# Sheet3.net
KiCad netlist of a schematic drawn in Altium Designer
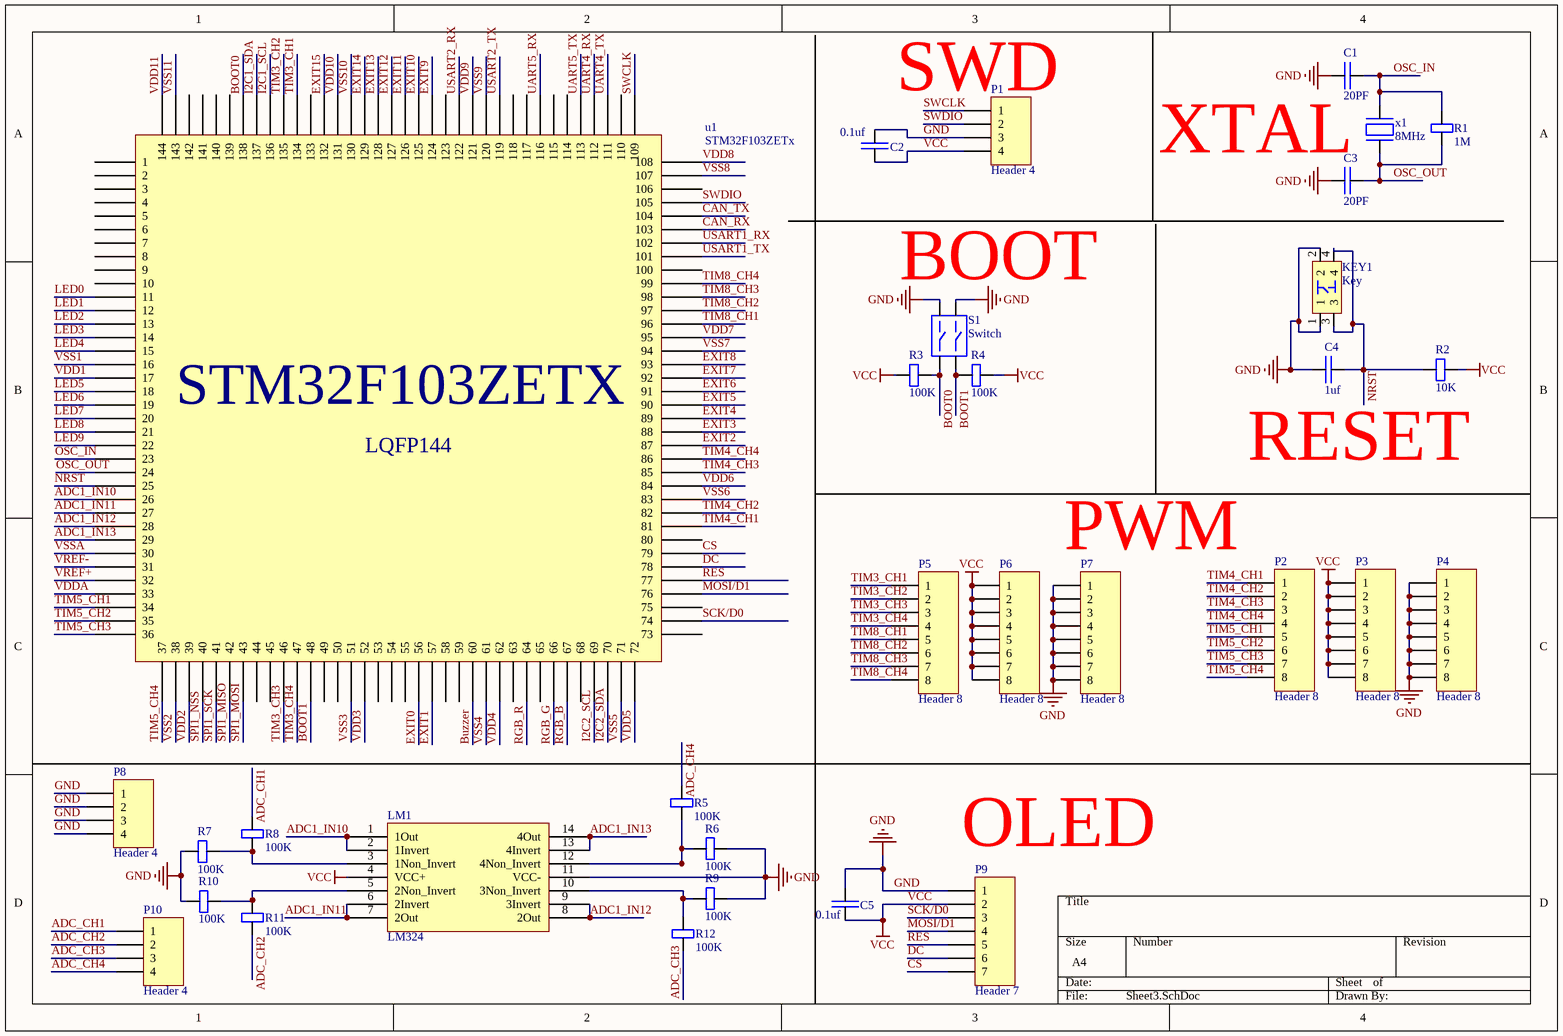
[diagram p0: Sheet3.SchDoc]

(export (version "E")
  (design (tool "Eeschema 10.0.6"))
  (components
    (comp (ref "C1") (value "20PF") (footprint "0402") (libsource (lib "Schlib1") (part "C")))
    (comp (ref "C2") (value "0.1uf") (footprint "0402") (libsource (lib "Schlib1") (part "C")))
    (comp (ref "C3") (value "20PF") (footprint "0402") (libsource (lib "Schlib1") (part "C")))
    (comp (ref "C4") (value "1uf") (footprint "0402") (libsource (lib "Schlib1") (part "C")))
    (comp (ref "C5") (value "0.1uf") (footprint "0402") (libsource (lib "Schlib1") (part "C")))
    (comp (ref "KEY1") (value "Key") (footprint "6*6*5轻触开关") (libsource (lib "Schlib1") (part "Key")))
    (comp (ref "LM1") (value "LM324") (footprint "LM324") (libsource (lib "Schlib1") (part "LM324")))
    (comp (ref "P1")
      (value "Header 4")
      (footprint "HDR1X4")
      (description "Header, 4-Pin")
      (fields (field (name "PUBLISHER") "Altium Limited"))
      (libsource (lib "Miscellaneous Connectors") (part "Header 4"))
    )
    (comp (ref "P2")
      (value "Header 8")
      (footprint "HDR1X8")
      (description "Header, 8-Pin")
      (fields (field (name "PUBLISHER") "Altium Limited"))
      (libsource (lib "Miscellaneous Connectors") (part "Header 8"))
    )
    (comp (ref "P3")
      (value "Header 8")
      (footprint "HDR1X8")
      (description "Header, 8-Pin")
      (fields (field (name "PUBLISHER") "Altium Limited"))
      (libsource (lib "Miscellaneous Connectors") (part "Header 8"))
    )
    (comp (ref "P4")
      (value "Header 8")
      (footprint "HDR1X8")
      (description "Header, 8-Pin")
      (fields (field (name "PUBLISHER") "Altium Limited"))
      (libsource (lib "Miscellaneous Connectors") (part "Header 8"))
    )
    (comp (ref "P5")
      (value "Header 8")
      (footprint "HDR1X8")
      (description "Header, 8-Pin")
      (fields (field (name "PUBLISHER") "Altium Limited"))
      (libsource (lib "Miscellaneous Connectors") (part "Header 8"))
    )
    (comp (ref "P6")
      (value "Header 8")
      (footprint "HDR1X8")
      (description "Header, 8-Pin")
      (fields (field (name "PUBLISHER") "Altium Limited"))
      (libsource (lib "Miscellaneous Connectors") (part "Header 8"))
    )
    (comp (ref "P7")
      (value "Header 8")
      (footprint "HDR1X8")
      (description "Header, 8-Pin")
      (fields (field (name "PUBLISHER") "Altium Limited"))
      (libsource (lib "Miscellaneous Connectors") (part "Header 8"))
    )
    (comp (ref "P8")
      (value "Header 4")
      (footprint "HDR1X4")
      (description "Header, 4-Pin")
      (fields (field (name "PUBLISHER") "Altium Limited"))
      (libsource (lib "Miscellaneous Connectors") (part "Header 4"))
    )
    (comp (ref "P9")
      (value "Header 7")
      (footprint "HDR1X7")
      (description "Header, 7-Pin")
      (fields (field (name "PUBLISHER") "Altium Limited"))
      (libsource (lib "Miscellaneous Connectors") (part "Header 7"))
    )
    (comp (ref "P10")
      (value "Header 4")
      (footprint "HDR1X4")
      (description "Header, 4-Pin")
      (fields (field (name "PUBLISHER") "Altium Limited"))
      (libsource (lib "Miscellaneous Connectors") (part "Header 4"))
    )
    (comp (ref "R1") (value "1M") (footprint "0402") (libsource (lib "Schlib1") (part "R")))
    (comp (ref "R2") (value "10K") (footprint "0402") (libsource (lib "Schlib1") (part "R")))
    (comp (ref "R3") (value "100K") (footprint "0402") (libsource (lib "Schlib1") (part "R")))
    (comp (ref "R4") (value "100K") (footprint "0402") (libsource (lib "Schlib1") (part "R")))
    (comp (ref "R5") (value "100K") (footprint "0402") (libsource (lib "Schlib1") (part "R")))
    (comp (ref "R6") (value "100K") (footprint "0402") (libsource (lib "Schlib1") (part "R")))
    (comp (ref "R7") (value "100K") (footprint "0402") (libsource (lib "Schlib1") (part "R")))
    (comp (ref "R8") (value "100K") (footprint "0402") (libsource (lib "Schlib1") (part "R")))
    (comp (ref "R9") (value "100K") (footprint "0402") (libsource (lib "Schlib1") (part "R")))
    (comp (ref "R10") (value "100K") (footprint "0402") (libsource (lib "Schlib1") (part "R")))
    (comp (ref "R11") (value "100K") (footprint "0402") (libsource (lib "Schlib1") (part "R")))
    (comp (ref "R12") (value "100K") (footprint "0402") (libsource (lib "Schlib1") (part "R")))
    (comp (ref "S1") (value "Switch") (footprint "SWITCH_2P") (libsource (lib "Schlib1") (part "Switch")))
    (comp (ref "u1")
      (value "STM32F103ZETx")
      (footprint "STM32F103ZETx")
      (libsource (lib "Schlib1") (part "STM32F103ZETx"))
    )
    (comp (ref "x1") (value "8MHz") (footprint "8M晶振") (libsource (lib "Schlib1") (part "XTAL_8MHz")))
  )
  (nets
    (net (code "1") (name "/ADC1_IN10") (class "Default")
      (node (ref "LM1") (pin "1") (pinfunction "1Out_1") (pintype "passive"))
      (node (ref "LM1") (pin "2") (pinfunction "1Invert_2") (pintype "passive"))
      (node (ref "u1") (pin "26") (pinfunction "26_26") (pintype "passive"))
    )
    (net (code "2") (name "/ADC1_IN11") (class "Default")
      (node (ref "LM1") (pin "6") (pinfunction "2Invert_6") (pintype "passive"))
      (node (ref "LM1") (pin "7") (pinfunction "2Out_7") (pintype "passive"))
      (node (ref "u1") (pin "27") (pinfunction "27_27") (pintype "passive"))
    )
    (net (code "3") (name "/ADC1_IN12") (class "Default")
      (node (ref "LM1") (pin "8") (pinfunction "2Out_8") (pintype "passive"))
      (node (ref "LM1") (pin "9") (pinfunction "3Invert_9") (pintype "passive"))
      (node (ref "u1") (pin "28") (pinfunction "28_28") (pintype "passive"))
    )
    (net (code "4") (name "/ADC1_IN13") (class "Default")
      (node (ref "LM1") (pin "13") (pinfunction "4Invert_13") (pintype "passive"))
      (node (ref "LM1") (pin "14") (pinfunction "4Out_14") (pintype "passive"))
      (node (ref "u1") (pin "29") (pinfunction "29_29") (pintype "passive"))
    )
    (net (code "5") (name "/ADC_CH1") (class "Default")
      (node (ref "P10") (pin "1") (pinfunction "1_1") (pintype "passive"))
      (node (ref "R8") (pin "2") (pinfunction "2_2") (pintype "passive"))
    )
    (net (code "6") (name "/ADC_CH2") (class "Default")
      (node (ref "P10") (pin "2") (pinfunction "2_2") (pintype "passive"))
      (node (ref "R11") (pin "2") (pinfunction "2_2") (pintype "passive"))
    )
    (net (code "7") (name "/ADC_CH3") (class "Default")
      (node (ref "P10") (pin "3") (pinfunction "3_3") (pintype "passive"))
      (node (ref "R12") (pin "2") (pinfunction "2_2") (pintype "passive"))
    )
    (net (code "8") (name "/ADC_CH4") (class "Default")
      (node (ref "P10") (pin "4") (pinfunction "4_4") (pintype "passive"))
      (node (ref "R5") (pin "1") (pinfunction "1_1") (pintype "passive"))
    )
    (net (code "9") (name "/BOOT0") (class "Default")
      (node (ref "R3") (pin "1") (pinfunction "1_1") (pintype "passive"))
      (node (ref "S1") (pin "2") (pinfunction "156_2") (pintype "passive"))
      (node (ref "u1") (pin "138") (pinfunction "138_138") (pintype "passive"))
    )
    (net (code "10") (name "/BOOT1") (class "Default")
      (node (ref "R4") (pin "2") (pinfunction "2_2") (pintype "passive"))
      (node (ref "S1") (pin "4") (pinfunction "157_4") (pintype "passive"))
      (node (ref "u1") (pin "48") (pinfunction "48_48") (pintype "passive"))
    )
    (net (code "11") (name "/Buzzer") (class "Default")
      (node (ref "u1") (pin "60") (pinfunction "60_60") (pintype "passive"))
    )
    (net (code "12") (name "/CAN_RX") (class "Default")
      (node (ref "u1") (pin "103") (pinfunction "103_103") (pintype "passive"))
    )
    (net (code "13") (name "/CAN_TX") (class "Default")
      (node (ref "u1") (pin "104") (pinfunction "104_104") (pintype "passive"))
    )
    (net (code "14") (name "/CS") (class "Default")
      (node (ref "P9") (pin "7") (pinfunction "7_7") (pintype "passive"))
      (node (ref "u1") (pin "79") (pinfunction "79_79") (pintype "passive"))
    )
    (net (code "15") (name "/DC") (class "Default")
      (node (ref "P9") (pin "6") (pinfunction "6_6") (pintype "passive"))
      (node (ref "u1") (pin "78") (pinfunction "78_78") (pintype "passive"))
    )
    (net (code "16") (name "/EXIT0") (class "Default")
      (node (ref "u1") (pin "56") (pinfunction "56_56") (pintype "passive"))
    )
    (net (code "17") (name "/EXIT1") (class "Default")
      (node (ref "u1") (pin "57") (pinfunction "57_57") (pintype "passive"))
    )
    (net (code "18") (name "/EXIT2") (class "Default")
      (node (ref "u1") (pin "87") (pinfunction "87_87") (pintype "passive"))
    )
    (net (code "19") (name "/EXIT3") (class "Default")
      (node (ref "u1") (pin "88") (pinfunction "88_88") (pintype "passive"))
    )
    (net (code "20") (name "/EXIT4") (class "Default")
      (node (ref "u1") (pin "89") (pinfunction "89_89") (pintype "passive"))
    )
    (net (code "21") (name "/EXIT5") (class "Default")
      (node (ref "u1") (pin "90") (pinfunction "90_90") (pintype "passive"))
    )
    (net (code "22") (name "/EXIT6") (class "Default")
      (node (ref "u1") (pin "91") (pinfunction "91_91") (pintype "passive"))
    )
    (net (code "23") (name "/EXIT7") (class "Default")
      (node (ref "u1") (pin "92") (pinfunction "92_92") (pintype "passive"))
    )
    (net (code "24") (name "/EXIT8") (class "Default")
      (node (ref "u1") (pin "93") (pinfunction "93_93") (pintype "passive"))
    )
    (net (code "25") (name "/EXIT9") (class "Default")
      (node (ref "u1") (pin "124") (pinfunction "124_124") (pintype "passive"))
    )
    (net (code "26") (name "/EXIT10") (class "Default")
      (node (ref "u1") (pin "125") (pinfunction "125_125") (pintype "passive"))
    )
    (net (code "27") (name "/EXIT11") (class "Default")
      (node (ref "u1") (pin "126") (pinfunction "126_126") (pintype "passive"))
    )
    (net (code "28") (name "/EXIT12") (class "Default")
      (node (ref "u1") (pin "127") (pinfunction "127_127") (pintype "passive"))
    )
    (net (code "29") (name "/EXIT13") (class "Default")
      (node (ref "u1") (pin "128") (pinfunction "128_128") (pintype "passive"))
    )
    (net (code "30") (name "/EXIT14") (class "Default")
      (node (ref "u1") (pin "129") (pinfunction "129_129") (pintype "passive"))
    )
    (net (code "31") (name "/EXIT15") (class "Default")
      (node (ref "u1") (pin "132") (pinfunction "132_132") (pintype "passive"))
    )
    (net (code "32") (name "/I2C1_SCL") (class "Default")
      (node (ref "u1") (pin "136") (pinfunction "136_136") (pintype "passive"))
    )
    (net (code "33") (name "/I2C1_SDA") (class "Default")
      (node (ref "u1") (pin "137") (pinfunction "137_137") (pintype "passive"))
    )
    (net (code "34") (name "/I2C2_SCL") (class "Default")
      (node (ref "u1") (pin "69") (pinfunction "69_69") (pintype "passive"))
    )
    (net (code "35") (name "/I2C2_SDA") (class "Default")
      (node (ref "u1") (pin "70") (pinfunction "70_70") (pintype "passive"))
    )
    (net (code "36") (name "/LED0") (class "Default")
      (node (ref "u1") (pin "11") (pinfunction "11_11") (pintype "passive"))
    )
    (net (code "37") (name "/LED1") (class "Default")
      (node (ref "u1") (pin "12") (pinfunction "12_12") (pintype "passive"))
    )
    (net (code "38") (name "/LED2") (class "Default")
      (node (ref "u1") (pin "13") (pinfunction "13_13") (pintype "passive"))
    )
    (net (code "39") (name "/LED3") (class "Default")
      (node (ref "u1") (pin "14") (pinfunction "14_14") (pintype "passive"))
    )
    (net (code "40") (name "/LED4") (class "Default")
      (node (ref "u1") (pin "15") (pinfunction "15_15") (pintype "passive"))
    )
    (net (code "41") (name "/LED5") (class "Default")
      (node (ref "u1") (pin "18") (pinfunction "18_18") (pintype "passive"))
    )
    (net (code "42") (name "/LED6") (class "Default")
      (node (ref "u1") (pin "19") (pinfunction "19_19") (pintype "passive"))
    )
    (net (code "43") (name "/LED7") (class "Default")
      (node (ref "u1") (pin "20") (pinfunction "20_20") (pintype "passive"))
    )
    (net (code "44") (name "/LED8") (class "Default")
      (node (ref "u1") (pin "21") (pinfunction "21_21") (pintype "passive"))
    )
    (net (code "45") (name "/LED9") (class "Default")
      (node (ref "u1") (pin "22") (pinfunction "22_22") (pintype "passive"))
    )
    (net (code "46") (name "/MOSI{slash}D1") (class "Default")
      (node (ref "P9") (pin "4") (pinfunction "4_4") (pintype "passive"))
      (node (ref "u1") (pin "76") (pinfunction "76_76") (pintype "passive"))
    )
    (net (code "47") (name "/NRST") (class "Default")
      (node (ref "C4") (pin "1") (pinfunction "1_1") (pintype "passive"))
      (node (ref "KEY1") (pin "3") (pinfunction "3_3") (pintype "passive"))
      (node (ref "KEY1") (pin "4") (pinfunction "4_4") (pintype "passive"))
      (node (ref "R2") (pin "1") (pinfunction "1_1") (pintype "passive"))
      (node (ref "u1") (pin "25") (pinfunction "25_25") (pintype "passive"))
    )
    (net (code "48") (name "/OSC_IN") (class "Default")
      (node (ref "C1") (pin "1") (pinfunction "1_1") (pintype "passive"))
      (node (ref "R1") (pin "2") (pinfunction "2_2") (pintype "passive"))
      (node (ref "u1") (pin "23") (pinfunction "23_23") (pintype "passive"))
      (node (ref "x1") (pin "1") (pinfunction "1_1") (pintype "passive"))
    )
    (net (code "49") (name "/OSC_OUT") (class "Default")
      (node (ref "C3") (pin "1") (pinfunction "1_1") (pintype "passive"))
      (node (ref "R1") (pin "1") (pinfunction "1_1") (pintype "passive"))
      (node (ref "u1") (pin "24") (pinfunction "24_24") (pintype "passive"))
      (node (ref "x1") (pin "2") (pinfunction "2_2") (pintype "passive"))
    )
    (net (code "50") (name "/RES") (class "Default")
      (node (ref "P9") (pin "5") (pinfunction "5_5") (pintype "passive"))
      (node (ref "u1") (pin "77") (pinfunction "77_77") (pintype "passive"))
    )
    (net (code "51") (name "/RGB_B") (class "Default")
      (node (ref "u1") (pin "67") (pinfunction "67_67") (pintype "passive"))
    )
    (net (code "52") (name "/RGB_G") (class "Default")
      (node (ref "u1") (pin "66") (pinfunction "66_66") (pintype "passive"))
    )
    (net (code "53") (name "/RGB_R") (class "Default")
      (node (ref "u1") (pin "64") (pinfunction "64_64") (pintype "passive"))
    )
    (net (code "54") (name "/SCK{slash}D0") (class "Default")
      (node (ref "P9") (pin "3") (pinfunction "3_3") (pintype "passive"))
      (node (ref "u1") (pin "74") (pinfunction "74_74") (pintype "passive"))
    )
    (net (code "55") (name "/SPI1_MISO") (class "Default")
      (node (ref "u1") (pin "42") (pinfunction "42_42") (pintype "passive"))
    )
    (net (code "56") (name "/SPI1_MOSI") (class "Default")
      (node (ref "u1") (pin "43") (pinfunction "43_43") (pintype "passive"))
    )
    (net (code "57") (name "/SPI1_NSS") (class "Default")
      (node (ref "u1") (pin "40") (pinfunction "40_40") (pintype "passive"))
    )
    (net (code "58") (name "/SPI1_SCK") (class "Default")
      (node (ref "u1") (pin "41") (pinfunction "41_41") (pintype "passive"))
    )
    (net (code "59") (name "/SWCLK") (class "Default")
      (node (ref "P1") (pin "1") (pinfunction "1_1") (pintype "passive"))
      (node (ref "u1") (pin "109") (pinfunction "109_109") (pintype "passive"))
    )
    (net (code "60") (name "/SWDIO") (class "Default")
      (node (ref "P1") (pin "2") (pinfunction "2_2") (pintype "passive"))
      (node (ref "u1") (pin "105") (pinfunction "105_105") (pintype "passive"))
    )
    (net (code "61") (name "/TIM3_CH1") (class "Default")
      (node (ref "P5") (pin "1") (pinfunction "1_1") (pintype "passive"))
      (node (ref "u1") (pin "134") (pinfunction "134_134") (pintype "passive"))
    )
    (net (code "62") (name "/TIM3_CH2") (class "Default")
      (node (ref "P5") (pin "2") (pinfunction "2_2") (pintype "passive"))
      (node (ref "u1") (pin "135") (pinfunction "135_135") (pintype "passive"))
    )
    (net (code "63") (name "/TIM3_CH3") (class "Default")
      (node (ref "P5") (pin "3") (pinfunction "3_3") (pintype "passive"))
      (node (ref "u1") (pin "46") (pinfunction "46_46") (pintype "passive"))
    )
    (net (code "64") (name "/TIM3_CH4") (class "Default")
      (node (ref "P5") (pin "4") (pinfunction "4_4") (pintype "passive"))
      (node (ref "u1") (pin "47") (pinfunction "47_47") (pintype "passive"))
    )
    (net (code "65") (name "/TIM4_CH1") (class "Default")
      (node (ref "P2") (pin "1") (pinfunction "1_1") (pintype "passive"))
      (node (ref "u1") (pin "81") (pinfunction "81_81") (pintype "passive"))
    )
    (net (code "66") (name "/TIM4_CH2") (class "Default")
      (node (ref "P2") (pin "2") (pinfunction "2_2") (pintype "passive"))
      (node (ref "u1") (pin "82") (pinfunction "82_82") (pintype "passive"))
    )
    (net (code "67") (name "/TIM4_CH3") (class "Default")
      (node (ref "P2") (pin "3") (pinfunction "3_3") (pintype "passive"))
      (node (ref "u1") (pin "85") (pinfunction "85_85") (pintype "passive"))
    )
    (net (code "68") (name "/TIM4_CH4") (class "Default")
      (node (ref "P2") (pin "4") (pinfunction "4_4") (pintype "passive"))
      (node (ref "u1") (pin "86") (pinfunction "86_86") (pintype "passive"))
    )
    (net (code "69") (name "/TIM5_CH1") (class "Default")
      (node (ref "P2") (pin "5") (pinfunction "5_5") (pintype "passive"))
      (node (ref "u1") (pin "34") (pinfunction "34_34") (pintype "passive"))
    )
    (net (code "70") (name "/TIM5_CH2") (class "Default")
      (node (ref "P2") (pin "6") (pinfunction "6_6") (pintype "passive"))
      (node (ref "u1") (pin "35") (pinfunction "35_35") (pintype "passive"))
    )
    (net (code "71") (name "/TIM5_CH3") (class "Default")
      (node (ref "P2") (pin "7") (pinfunction "7_7") (pintype "passive"))
      (node (ref "u1") (pin "36") (pinfunction "36_36") (pintype "passive"))
    )
    (net (code "72") (name "/TIM5_CH4") (class "Default")
      (node (ref "P2") (pin "8") (pinfunction "8_8") (pintype "passive"))
      (node (ref "u1") (pin "37") (pinfunction "37_37") (pintype "passive"))
    )
    (net (code "73") (name "/TIM8_CH1") (class "Default")
      (node (ref "P5") (pin "5") (pinfunction "5_5") (pintype "passive"))
      (node (ref "u1") (pin "96") (pinfunction "96_96") (pintype "passive"))
    )
    (net (code "74") (name "/TIM8_CH2") (class "Default")
      (node (ref "P5") (pin "6") (pinfunction "6_6") (pintype "passive"))
      (node (ref "u1") (pin "97") (pinfunction "97_97") (pintype "passive"))
    )
    (net (code "75") (name "/TIM8_CH3") (class "Default")
      (node (ref "P5") (pin "7") (pinfunction "7_7") (pintype "passive"))
      (node (ref "u1") (pin "98") (pinfunction "98_98") (pintype "passive"))
    )
    (net (code "76") (name "/TIM8_CH4") (class "Default")
      (node (ref "P5") (pin "8") (pinfunction "8_8") (pintype "passive"))
      (node (ref "u1") (pin "99") (pinfunction "99_99") (pintype "passive"))
    )
    (net (code "77") (name "/UART4_RX") (class "Default")
      (node (ref "u1") (pin "112") (pinfunction "112_112") (pintype "passive"))
    )
    (net (code "78") (name "/UART4_TX") (class "Default")
      (node (ref "u1") (pin "111") (pinfunction "111_111") (pintype "passive"))
    )
    (net (code "79") (name "/UART5_RX") (class "Default")
      (node (ref "u1") (pin "116") (pinfunction "116_116") (pintype "passive"))
    )
    (net (code "80") (name "/UART5_TX") (class "Default")
      (node (ref "u1") (pin "113") (pinfunction "113_113") (pintype "passive"))
    )
    (net (code "81") (name "/USART1_RX") (class "Default")
      (node (ref "u1") (pin "102") (pinfunction "102_102") (pintype "passive"))
    )
    (net (code "82") (name "/USART1_TX") (class "Default")
      (node (ref "u1") (pin "101") (pinfunction "101_101") (pintype "passive"))
    )
    (net (code "83") (name "/USART2_RX") (class "Default")
      (node (ref "u1") (pin "122") (pinfunction "122_122") (pintype "passive"))
    )
    (net (code "84") (name "/USART2_TX") (class "Default")
      (node (ref "u1") (pin "119") (pinfunction "119_119") (pintype "passive"))
    )
    (net (code "85") (name "/VDD1") (class "Default")
      (node (ref "u1") (pin "17") (pinfunction "17_17") (pintype "passive"))
    )
    (net (code "86") (name "/VDD2") (class "Default")
      (node (ref "u1") (pin "39") (pinfunction "39_39") (pintype "passive"))
    )
    (net (code "87") (name "/VDD3") (class "Default")
      (node (ref "u1") (pin "52") (pinfunction "52_52") (pintype "passive"))
    )
    (net (code "88") (name "/VDD4") (class "Default")
      (node (ref "u1") (pin "62") (pinfunction "62_62") (pintype "passive"))
    )
    (net (code "89") (name "/VDD5") (class "Default")
      (node (ref "u1") (pin "72") (pinfunction "72_72") (pintype "passive"))
    )
    (net (code "90") (name "/VDD6") (class "Default")
      (node (ref "u1") (pin "84") (pinfunction "84_84") (pintype "passive"))
    )
    (net (code "91") (name "/VDD7") (class "Default")
      (node (ref "u1") (pin "95") (pinfunction "95_95") (pintype "passive"))
    )
    (net (code "92") (name "/VDD8") (class "Default")
      (node (ref "u1") (pin "108") (pinfunction "108_108") (pintype "passive"))
    )
    (net (code "93") (name "/VDD9") (class "Default")
      (node (ref "u1") (pin "121") (pinfunction "121_121") (pintype "passive"))
    )
    (net (code "94") (name "/VDD10") (class "Default")
      (node (ref "u1") (pin "131") (pinfunction "131_131") (pintype "passive"))
    )
    (net (code "95") (name "/VDD11") (class "Default")
      (node (ref "u1") (pin "144") (pinfunction "144_144") (pintype "passive"))
    )
    (net (code "96") (name "/VDDA") (class "Default")
      (node (ref "u1") (pin "33") (pinfunction "33_33") (pintype "passive"))
    )
    (net (code "97") (name "/VREF+") (class "Default")
      (node (ref "u1") (pin "32") (pinfunction "32_32") (pintype "passive"))
    )
    (net (code "98") (name "/VREF-") (class "Default")
      (node (ref "u1") (pin "31") (pinfunction "31_31") (pintype "passive"))
    )
    (net (code "99") (name "/VSS1") (class "Default")
      (node (ref "u1") (pin "16") (pinfunction "16_16") (pintype "passive"))
    )
    (net (code "100") (name "/VSS2") (class "Default")
      (node (ref "u1") (pin "38") (pinfunction "38_38") (pintype "passive"))
    )
    (net (code "101") (name "/VSS3") (class "Default")
      (node (ref "u1") (pin "51") (pinfunction "51_51") (pintype "passive"))
    )
    (net (code "102") (name "/VSS4") (class "Default")
      (node (ref "u1") (pin "61") (pinfunction "61_61") (pintype "passive"))
    )
    (net (code "103") (name "/VSS5") (class "Default")
      (node (ref "u1") (pin "71") (pinfunction "71_71") (pintype "passive"))
    )
    (net (code "104") (name "/VSS6") (class "Default")
      (node (ref "u1") (pin "83") (pinfunction "83_83") (pintype "passive"))
    )
    (net (code "105") (name "/VSS7") (class "Default")
      (node (ref "u1") (pin "94") (pinfunction "94_94") (pintype "passive"))
    )
    (net (code "106") (name "/VSS8") (class "Default")
      (node (ref "u1") (pin "107") (pinfunction "107_107") (pintype "passive"))
    )
    (net (code "107") (name "/VSS9") (class "Default")
      (node (ref "u1") (pin "120") (pinfunction "120_120") (pintype "passive"))
    )
    (net (code "108") (name "/VSS10") (class "Default")
      (node (ref "u1") (pin "130") (pinfunction "130_130") (pintype "passive"))
    )
    (net (code "109") (name "/VSS11") (class "Default")
      (node (ref "u1") (pin "143") (pinfunction "143_143") (pintype "passive"))
    )
    (net (code "110") (name "/VSSA") (class "Default")
      (node (ref "u1") (pin "30") (pinfunction "30_30") (pintype "passive"))
    )
    (net (code "111") (name "GND") (class "Default")
      (node (ref "C1") (pin "2") (pinfunction "2_2") (pintype "passive"))
      (node (ref "C2") (pin "1") (pinfunction "1_1") (pintype "passive"))
      (node (ref "C3") (pin "2") (pinfunction "2_2") (pintype "passive"))
      (node (ref "C4") (pin "2") (pinfunction "2_2") (pintype "passive"))
      (node (ref "C5") (pin "1") (pinfunction "1_1") (pintype "passive"))
      (node (ref "KEY1") (pin "1") (pinfunction "1_1") (pintype "passive"))
      (node (ref "KEY1") (pin "2") (pinfunction "2_2") (pintype "passive"))
      (node (ref "LM1") (pin "11") (pinfunction "VCC-_11") (pintype "passive"))
      (node (ref "P1") (pin "3") (pinfunction "3_3") (pintype "passive"))
      (node (ref "P4") (pin "1") (pinfunction "1_1") (pintype "passive"))
      (node (ref "P4") (pin "2") (pinfunction "2_2") (pintype "passive"))
      (node (ref "P4") (pin "3") (pinfunction "3_3") (pintype "passive"))
      (node (ref "P4") (pin "4") (pinfunction "4_4") (pintype "passive"))
      (node (ref "P4") (pin "5") (pinfunction "5_5") (pintype "passive"))
      (node (ref "P4") (pin "6") (pinfunction "6_6") (pintype "passive"))
      (node (ref "P4") (pin "7") (pinfunction "7_7") (pintype "passive"))
      (node (ref "P4") (pin "8") (pinfunction "8_8") (pintype "passive"))
      (node (ref "P7") (pin "1") (pinfunction "1_1") (pintype "passive"))
      (node (ref "P7") (pin "2") (pinfunction "2_2") (pintype "passive"))
      (node (ref "P7") (pin "3") (pinfunction "3_3") (pintype "passive"))
      (node (ref "P7") (pin "4") (pinfunction "4_4") (pintype "passive"))
      (node (ref "P7") (pin "5") (pinfunction "5_5") (pintype "passive"))
      (node (ref "P7") (pin "6") (pinfunction "6_6") (pintype "passive"))
      (node (ref "P7") (pin "7") (pinfunction "7_7") (pintype "passive"))
      (node (ref "P7") (pin "8") (pinfunction "8_8") (pintype "passive"))
      (node (ref "P8") (pin "1") (pinfunction "1_1") (pintype "passive"))
      (node (ref "P8") (pin "2") (pinfunction "2_2") (pintype "passive"))
      (node (ref "P8") (pin "3") (pinfunction "3_3") (pintype "passive"))
      (node (ref "P8") (pin "4") (pinfunction "4_4") (pintype "passive"))
      (node (ref "P9") (pin "1") (pinfunction "1_1") (pintype "passive"))
      (node (ref "R10") (pin "1") (pinfunction "1_1") (pintype "passive"))
      (node (ref "R6") (pin "1") (pinfunction "1_1") (pintype "passive"))
      (node (ref "R7") (pin "1") (pinfunction "1_1") (pintype "passive"))
      (node (ref "R9") (pin "1") (pinfunction "1_1") (pintype "passive"))
      (node (ref "S1") (pin "1") (pinfunction "154_1") (pintype "passive"))
      (node (ref "S1") (pin "3") (pinfunction "155_3") (pintype "passive"))
    )
    (net (code "112") (name "Net-(LM1-1Non_Invert)") (class "Default")
      (node (ref "LM1") (pin "3") (pinfunction "1Non_Invert_3") (pintype "passive"))
      (node (ref "R7") (pin "2") (pinfunction "2_2") (pintype "passive"))
      (node (ref "R8") (pin "1") (pinfunction "1_1") (pintype "passive"))
    )
    (net (code "113") (name "Net-(LM1-2Non_Invert)") (class "Default")
      (node (ref "LM1") (pin "5") (pinfunction "2Non_Invert_5") (pintype "passive"))
      (node (ref "R10") (pin "2") (pinfunction "2_2") (pintype "passive"))
      (node (ref "R11") (pin "1") (pinfunction "1_1") (pintype "passive"))
    )
    (net (code "114") (name "Net-(LM1-3Non_Invert)") (class "Default")
      (node (ref "LM1") (pin "10") (pinfunction "3Non_Invert_10") (pintype "passive"))
      (node (ref "R12") (pin "1") (pinfunction "1_1") (pintype "passive"))
      (node (ref "R9") (pin "2") (pinfunction "2_2") (pintype "passive"))
    )
    (net (code "115") (name "Net-(LM1-4Non_Invert)") (class "Default")
      (node (ref "LM1") (pin "12") (pinfunction "4Non_Invert_12") (pintype "passive"))
      (node (ref "R5") (pin "2") (pinfunction "2_2") (pintype "passive"))
      (node (ref "R6") (pin "2") (pinfunction "2_2") (pintype "passive"))
    )
    (net (code "116") (name "VCC") (class "Default")
      (node (ref "C2") (pin "2") (pinfunction "2_2") (pintype "passive"))
      (node (ref "C5") (pin "2") (pinfunction "2_2") (pintype "passive"))
      (node (ref "LM1") (pin "4") (pinfunction "VCC+_4") (pintype "passive"))
      (node (ref "P1") (pin "4") (pinfunction "4_4") (pintype "passive"))
      (node (ref "P3") (pin "1") (pinfunction "1_1") (pintype "passive"))
      (node (ref "P3") (pin "2") (pinfunction "2_2") (pintype "passive"))
      (node (ref "P3") (pin "3") (pinfunction "3_3") (pintype "passive"))
      (node (ref "P3") (pin "4") (pinfunction "4_4") (pintype "passive"))
      (node (ref "P3") (pin "5") (pinfunction "5_5") (pintype "passive"))
      (node (ref "P3") (pin "6") (pinfunction "6_6") (pintype "passive"))
      (node (ref "P3") (pin "7") (pinfunction "7_7") (pintype "passive"))
      (node (ref "P3") (pin "8") (pinfunction "8_8") (pintype "passive"))
      (node (ref "P6") (pin "1") (pinfunction "1_1") (pintype "passive"))
      (node (ref "P6") (pin "2") (pinfunction "2_2") (pintype "passive"))
      (node (ref "P6") (pin "3") (pinfunction "3_3") (pintype "passive"))
      (node (ref "P6") (pin "4") (pinfunction "4_4") (pintype "passive"))
      (node (ref "P6") (pin "5") (pinfunction "5_5") (pintype "passive"))
      (node (ref "P6") (pin "6") (pinfunction "6_6") (pintype "passive"))
      (node (ref "P6") (pin "7") (pinfunction "7_7") (pintype "passive"))
      (node (ref "P6") (pin "8") (pinfunction "8_8") (pintype "passive"))
      (node (ref "P9") (pin "2") (pinfunction "2_2") (pintype "passive"))
      (node (ref "R2") (pin "2") (pinfunction "2_2") (pintype "passive"))
      (node (ref "R3") (pin "2") (pinfunction "2_2") (pintype "passive"))
      (node (ref "R4") (pin "1") (pinfunction "1_1") (pintype "passive"))
    )
    (net (code "117") (name "unconnected-(u1-Pad1)") (class "Default")
      (node (ref "u1") (pin "1") (pinfunction "1_1") (pintype "passive"))
    )
    (net (code "118") (name "unconnected-(u1-Pad2)") (class "Default")
      (node (ref "u1") (pin "2") (pinfunction "2_2") (pintype "passive"))
    )
    (net (code "119") (name "unconnected-(u1-Pad3)") (class "Default")
      (node (ref "u1") (pin "3") (pinfunction "3_3") (pintype "passive"))
    )
    (net (code "120") (name "unconnected-(u1-Pad4)") (class "Default")
      (node (ref "u1") (pin "4") (pinfunction "4_4") (pintype "passive"))
    )
    (net (code "121") (name "unconnected-(u1-Pad5)") (class "Default")
      (node (ref "u1") (pin "5") (pinfunction "5_5") (pintype "passive"))
    )
    (net (code "122") (name "unconnected-(u1-Pad6)") (class "Default")
      (node (ref "u1") (pin "6") (pinfunction "6_6") (pintype "passive"))
    )
    (net (code "123") (name "unconnected-(u1-Pad7)") (class "Default")
      (node (ref "u1") (pin "7") (pinfunction "7_7") (pintype "passive"))
    )
    (net (code "124") (name "unconnected-(u1-Pad8)") (class "Default")
      (node (ref "u1") (pin "8") (pinfunction "8_8") (pintype "passive"))
    )
    (net (code "125") (name "unconnected-(u1-Pad9)") (class "Default")
      (node (ref "u1") (pin "9") (pinfunction "9_9") (pintype "passive"))
    )
    (net (code "126") (name "unconnected-(u1-Pad10)") (class "Default")
      (node (ref "u1") (pin "10") (pinfunction "10_10") (pintype "passive"))
    )
    (net (code "127") (name "unconnected-(u1-Pad44)") (class "Default")
      (node (ref "u1") (pin "44") (pinfunction "44_44") (pintype "passive"))
    )
    (net (code "128") (name "unconnected-(u1-Pad45)") (class "Default")
      (node (ref "u1") (pin "45") (pinfunction "45_45") (pintype "passive"))
    )
    (net (code "129") (name "unconnected-(u1-Pad49)") (class "Default")
      (node (ref "u1") (pin "49") (pinfunction "49_49") (pintype "passive"))
    )
    (net (code "130") (name "unconnected-(u1-Pad50)") (class "Default")
      (node (ref "u1") (pin "50") (pinfunction "50_50") (pintype "passive"))
    )
    (net (code "131") (name "unconnected-(u1-Pad53)") (class "Default")
      (node (ref "u1") (pin "53") (pinfunction "53_53") (pintype "passive"))
    )
    (net (code "132") (name "unconnected-(u1-Pad54)") (class "Default")
      (node (ref "u1") (pin "54") (pinfunction "54_54") (pintype "passive"))
    )
    (net (code "133") (name "unconnected-(u1-Pad55)") (class "Default")
      (node (ref "u1") (pin "55") (pinfunction "55_55") (pintype "passive"))
    )
    (net (code "134") (name "unconnected-(u1-Pad58)") (class "Default")
      (node (ref "u1") (pin "58") (pinfunction "58_58") (pintype "passive"))
    )
    (net (code "135") (name "unconnected-(u1-Pad59)") (class "Default")
      (node (ref "u1") (pin "59") (pinfunction "59_59") (pintype "passive"))
    )
    (net (code "136") (name "unconnected-(u1-Pad63)") (class "Default")
      (node (ref "u1") (pin "63") (pinfunction "63_63") (pintype "passive"))
    )
    (net (code "137") (name "unconnected-(u1-Pad65)") (class "Default")
      (node (ref "u1") (pin "65") (pinfunction "65_65") (pintype "passive"))
    )
    (net (code "138") (name "unconnected-(u1-Pad68)") (class "Default")
      (node (ref "u1") (pin "68") (pinfunction "68_68") (pintype "passive"))
    )
    (net (code "139") (name "unconnected-(u1-Pad73)") (class "Default")
      (node (ref "u1") (pin "73") (pinfunction "73_73") (pintype "passive"))
    )
    (net (code "140") (name "unconnected-(u1-Pad75)") (class "Default")
      (node (ref "u1") (pin "75") (pinfunction "75_75") (pintype "passive"))
    )
    (net (code "141") (name "unconnected-(u1-Pad80)") (class "Default")
      (node (ref "u1") (pin "80") (pinfunction "80_80") (pintype "passive"))
    )
    (net (code "142") (name "unconnected-(u1-Pad100)") (class "Default")
      (node (ref "u1") (pin "100") (pinfunction "100_100") (pintype "passive"))
    )
    (net (code "143") (name "unconnected-(u1-Pad106)") (class "Default")
      (node (ref "u1") (pin "106") (pinfunction "106_106") (pintype "passive"))
    )
    (net (code "144") (name "unconnected-(u1-Pad110)") (class "Default")
      (node (ref "u1") (pin "110") (pinfunction "110_110") (pintype "passive"))
    )
    (net (code "145") (name "unconnected-(u1-Pad114)") (class "Default")
      (node (ref "u1") (pin "114") (pinfunction "114_114") (pintype "passive"))
    )
    (net (code "146") (name "unconnected-(u1-Pad115)") (class "Default")
      (node (ref "u1") (pin "115") (pinfunction "115_115") (pintype "passive"))
    )
    (net (code "147") (name "unconnected-(u1-Pad117)") (class "Default")
      (node (ref "u1") (pin "117") (pinfunction "117_117") (pintype "passive"))
    )
    (net (code "148") (name "unconnected-(u1-Pad118)") (class "Default")
      (node (ref "u1") (pin "118") (pinfunction "118_118") (pintype "passive"))
    )
    (net (code "149") (name "unconnected-(u1-Pad123)") (class "Default")
      (node (ref "u1") (pin "123") (pinfunction "123_123") (pintype "passive"))
    )
    (net (code "150") (name "unconnected-(u1-Pad133)") (class "Default")
      (node (ref "u1") (pin "133") (pinfunction "133_133") (pintype "passive"))
    )
    (net (code "151") (name "unconnected-(u1-Pad139)") (class "Default")
      (node (ref "u1") (pin "139") (pinfunction "139_139") (pintype "passive"))
    )
    (net (code "152") (name "unconnected-(u1-Pad140)") (class "Default")
      (node (ref "u1") (pin "140") (pinfunction "140_140") (pintype "passive"))
    )
    (net (code "153") (name "unconnected-(u1-Pad141)") (class "Default")
      (node (ref "u1") (pin "141") (pinfunction "141_141") (pintype "passive"))
    )
    (net (code "154") (name "unconnected-(u1-Pad142)") (class "Default")
      (node (ref "u1") (pin "142") (pinfunction "142_142") (pintype "passive"))
    )
  )
)
